# avrLCD.net
KiCad netlist of a schematic drawn in EAGLE
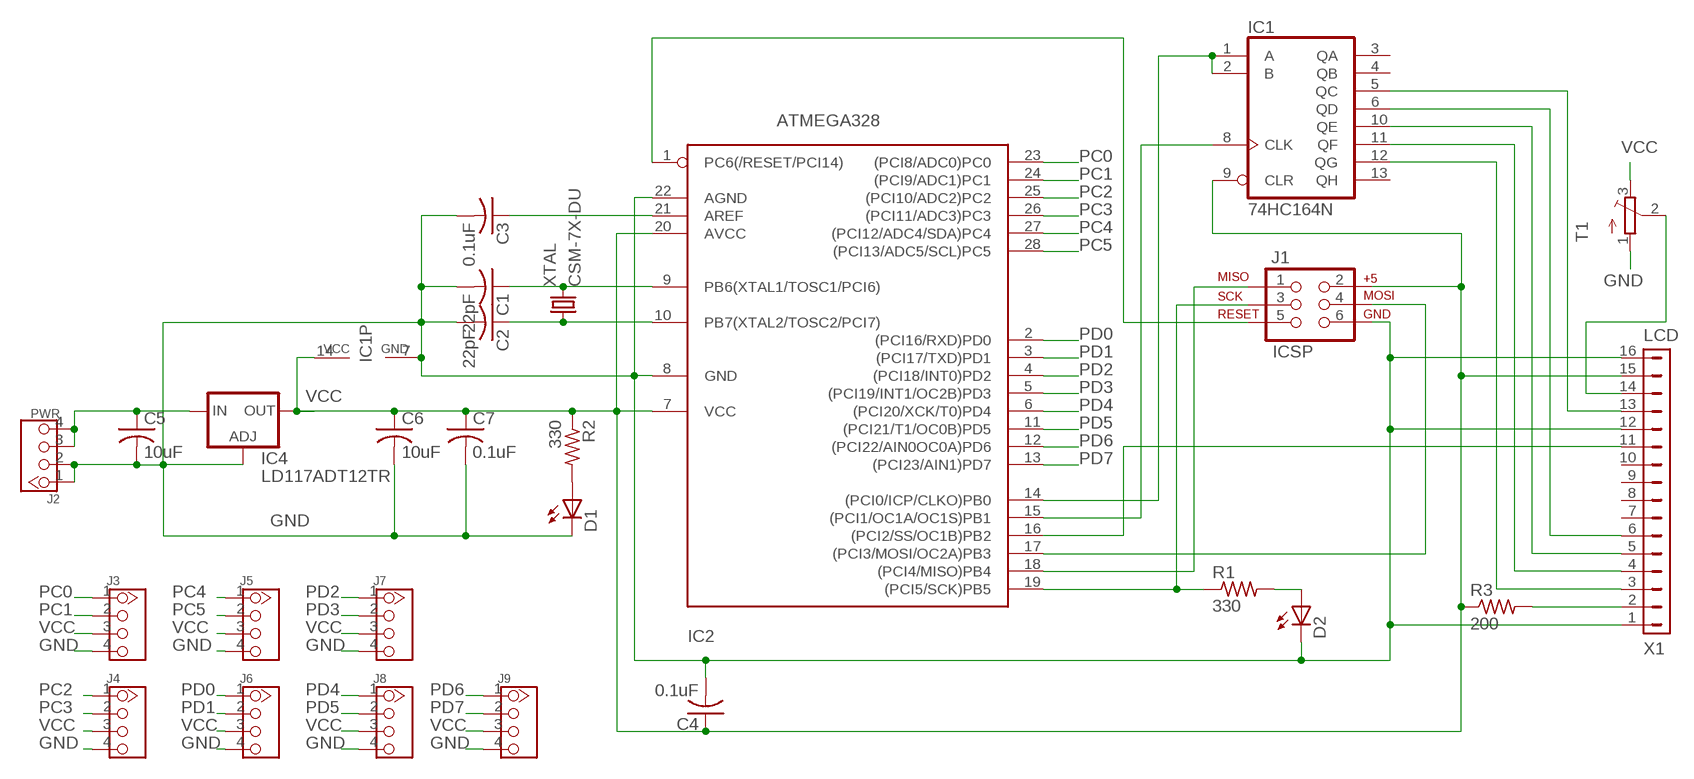
[diagram p0: schematic, sheet 1]

(export (version "E")
  (design (tool "Eeschema 10.0.6"))
  (components
    (comp (ref "C1")
      (value "22pF")
      (footprint "eagle-import:C0805")
      (libsource (lib "eagle-import") (part "C-USC0805"))
    )
    (comp (ref "C2")
      (value "22pF")
      (footprint "eagle-import:C0805")
      (libsource (lib "eagle-import") (part "C-USC0805"))
    )
    (comp (ref "C3")
      (value "0.1uF")
      (footprint "eagle-import:C0805")
      (libsource (lib "eagle-import") (part "C-USC0805"))
    )
    (comp (ref "C4")
      (value "0.1uF")
      (footprint "eagle-import:C0805")
      (libsource (lib "eagle-import") (part "C-USC0805"))
    )
    (comp (ref "C5")
      (value "10uF")
      (footprint "eagle-import:C1206")
      (libsource (lib "eagle-import") (part "C-USC1206"))
    )
    (comp (ref "C6")
      (value "10uF")
      (footprint "eagle-import:C1206")
      (libsource (lib "eagle-import") (part "C-USC1206"))
    )
    (comp (ref "C7")
      (value "0.1uF")
      (footprint "eagle-import:C0805")
      (libsource (lib "eagle-import") (part "C-USC0805"))
    )
    (comp (ref "D1")
      (value "LEDCHIP-LED0805")
      (footprint "eagle-import:CHIP-LED0805")
      (libsource (lib "eagle-import") (part "LEDCHIP-LED0805"))
    )
    (comp (ref "D2")
      (value "LEDCHIP-LED0805")
      (footprint "eagle-import:CHIP-LED0805")
      (libsource (lib "eagle-import") (part "LEDCHIP-LED0805"))
    )
    (comp (ref "IC1")
      (value "74HC164N")
      (footprint "eagle-import:DIL14")
      (libsource (lib "eagle-import") (part "74164NHC"))
    )
    (comp (ref "IC2")
      (value "ATMEGA328")
      (footprint "eagle-import:DIL28-3")
      (libsource (lib "eagle-import") (part "ATMEGA168P-20"))
    )
    (comp (ref "IC4")
      (value "LD117ADT12TR")
      (footprint "eagle-import:DPACK")
      (libsource (lib "eagle-import") (part "LD117A?DT12TR"))
    )
    (comp (ref "J1")
      (value "ICSP")
      (footprint "eagle-import:2X3-NS")
      (libsource (lib "eagle-import") (part "AVR_SPI_PRG_6NS"))
    )
    (comp (ref "J2")
      (value "PWR")
      (footprint "eagle-import:4P-2.0")
      (libsource (lib "eagle-import") (part "TWIG-4P-2.0-2.0"))
    )
    (comp (ref "J3")
      (value "TWIG-4P-2.0-2.0")
      (footprint "eagle-import:4P-2.0")
      (libsource (lib "eagle-import") (part "TWIG-4P-2.0-2.0"))
    )
    (comp (ref "J4")
      (value "TWIG-4P-2.0-2.0")
      (footprint "eagle-import:4P-2.0")
      (libsource (lib "eagle-import") (part "TWIG-4P-2.0-2.0"))
    )
    (comp (ref "J5")
      (value "TWIG-4P-2.0-2.0")
      (footprint "eagle-import:4P-2.0")
      (libsource (lib "eagle-import") (part "TWIG-4P-2.0-2.0"))
    )
    (comp (ref "J6")
      (value "TWIG-4P-2.0-2.0")
      (footprint "eagle-import:4P-2.0")
      (libsource (lib "eagle-import") (part "TWIG-4P-2.0-2.0"))
    )
    (comp (ref "J7")
      (value "TWIG-4P-2.0-2.0")
      (footprint "eagle-import:4P-2.0")
      (libsource (lib "eagle-import") (part "TWIG-4P-2.0-2.0"))
    )
    (comp (ref "J8")
      (value "TWIG-4P-2.0-2.0")
      (footprint "eagle-import:4P-2.0")
      (libsource (lib "eagle-import") (part "TWIG-4P-2.0-2.0"))
    )
    (comp (ref "J9")
      (value "TWIG-4P-2.0-2.0")
      (footprint "eagle-import:4P-2.0")
      (libsource (lib "eagle-import") (part "TWIG-4P-2.0-2.0"))
    )
    (comp (ref "R1")
      (value "330")
      (footprint "eagle-import:R0805")
      (libsource (lib "eagle-import") (part "R-US_R0805"))
    )
    (comp (ref "R2")
      (value "330")
      (footprint "eagle-import:R0805")
      (libsource (lib "eagle-import") (part "R-US_R0805"))
    )
    (comp (ref "R3")
      (value "200")
      (footprint "eagle-import:R1206")
      (libsource (lib "eagle-import") (part "R-US_R1206"))
    )
    (comp (ref "T1")
      (value "TRIMPOTTC33X")
      (footprint "eagle-import:TC33X")
      (libsource (lib "eagle-import") (part "TRIMPOTTC33X"))
    )
    (comp (ref "X1")
      (value "LCD")
      (footprint "eagle-import:FH21-16S-1DS")
      (libsource (lib "eagle-import") (part "FH21-16S-1DS"))
    )
    (comp (ref "XTAL")
      (value "CSM-7X-DU")
      (footprint "eagle-import:CSM-7X-DU")
      (libsource (lib "eagle-import") (part "CSM-7X-DU"))
    )
  )
  (nets
    (net (code "1") (name "/GND") (class "Default")
      (node (ref "C1") (pin "2") (pinfunction "2_2") (pintype "passive"))
      (node (ref "C2") (pin "2") (pinfunction "2_2") (pintype "passive"))
      (node (ref "C3") (pin "2") (pinfunction "2_2") (pintype "passive"))
      (node (ref "C4") (pin "2") (pinfunction "2_2") (pintype "passive"))
      (node (ref "C5") (pin "2") (pinfunction "2_2") (pintype "passive"))
      (node (ref "C6") (pin "2") (pinfunction "2_2") (pintype "passive"))
      (node (ref "C7") (pin "2") (pinfunction "2_2") (pintype "passive"))
      (node (ref "D1") (pin "C") (pinfunction "C_C") (pintype "passive"))
      (node (ref "D2") (pin "C") (pinfunction "C_C") (pintype "passive"))
      (node (ref "IC1") (pin "7") (pinfunction "GND_7") (pintype "power_in"))
      (node (ref "IC2") (pin "22") (pinfunction "AGND_22") (pintype "bidirectional"))
      (node (ref "IC2") (pin "8") (pinfunction "GND_8") (pintype "bidirectional"))
      (node (ref "IC4") (pin "1") (pinfunction "ADJ_1") (pintype "input"))
      (node (ref "J1") (pin "6") (pinfunction "6_6") (pintype "passive"))
      (node (ref "J2") (pin "1") (pinfunction "1_1") (pintype "bidirectional"))
      (node (ref "J2") (pin "2") (pinfunction "2_2") (pintype "bidirectional"))
      (node (ref "J3") (pin "4") (pinfunction "4_4") (pintype "bidirectional"))
      (node (ref "J4") (pin "4") (pinfunction "4_4") (pintype "bidirectional"))
      (node (ref "J5") (pin "4") (pinfunction "4_4") (pintype "bidirectional"))
      (node (ref "J6") (pin "4") (pinfunction "4_4") (pintype "bidirectional"))
      (node (ref "J7") (pin "4") (pinfunction "4_4") (pintype "bidirectional"))
      (node (ref "J8") (pin "4") (pinfunction "4_4") (pintype "bidirectional"))
      (node (ref "J9") (pin "4") (pinfunction "4_4") (pintype "bidirectional"))
      (node (ref "T1") (pin "1") (pinfunction "A_1") (pintype "passive"))
      (node (ref "X1") (pin "1") (pinfunction "1_1") (pintype "passive"))
      (node (ref "X1") (pin "12") (pinfunction "12_12") (pintype "passive"))
      (node (ref "X1") (pin "16") (pinfunction "16_16") (pintype "passive"))
    )
    (net (code "2") (name "/PC0") (class "Default")
      (node (ref "IC2") (pin "23") (pinfunction "(PCI8/ADC0)PC0_23") (pintype "bidirectional"))
      (node (ref "J3") (pin "1") (pinfunction "1_1") (pintype "bidirectional"))
    )
    (net (code "3") (name "/PC1") (class "Default")
      (node (ref "IC2") (pin "24") (pinfunction "(PCI9/ADC1)PC1_24") (pintype "bidirectional"))
      (node (ref "J3") (pin "2") (pinfunction "2_2") (pintype "bidirectional"))
    )
    (net (code "4") (name "/PC2") (class "Default")
      (node (ref "IC2") (pin "25") (pinfunction "(PCI10/ADC2)PC2_25") (pintype "bidirectional"))
      (node (ref "J4") (pin "1") (pinfunction "1_1") (pintype "bidirectional"))
    )
    (net (code "5") (name "/PC3") (class "Default")
      (node (ref "IC2") (pin "26") (pinfunction "(PCI11/ADC3)PC3_26") (pintype "bidirectional"))
      (node (ref "J4") (pin "2") (pinfunction "2_2") (pintype "bidirectional"))
    )
    (net (code "6") (name "/PC4") (class "Default")
      (node (ref "IC2") (pin "27") (pinfunction "(PCI12/ADC4/SDA)PC4_27") (pintype "bidirectional"))
      (node (ref "J5") (pin "1") (pinfunction "1_1") (pintype "bidirectional"))
    )
    (net (code "7") (name "/PC5") (class "Default")
      (node (ref "IC2") (pin "28") (pinfunction "(PCI13/ADC5/SCL)PC5_28") (pintype "bidirectional"))
      (node (ref "J5") (pin "2") (pinfunction "2_2") (pintype "bidirectional"))
    )
    (net (code "8") (name "/PD0") (class "Default")
      (node (ref "IC2") (pin "2") (pinfunction "(PCI16/RXD)PD0_2") (pintype "bidirectional"))
      (node (ref "J6") (pin "1") (pinfunction "1_1") (pintype "bidirectional"))
    )
    (net (code "9") (name "/PD1") (class "Default")
      (node (ref "IC2") (pin "3") (pinfunction "(PCI17/TXD)PD1_3") (pintype "bidirectional"))
      (node (ref "J6") (pin "2") (pinfunction "2_2") (pintype "bidirectional"))
    )
    (net (code "10") (name "/PD2") (class "Default")
      (node (ref "IC2") (pin "4") (pinfunction "(PCI18/INT0)PD2_4") (pintype "bidirectional"))
      (node (ref "J7") (pin "1") (pinfunction "1_1") (pintype "bidirectional"))
    )
    (net (code "11") (name "/PD3") (class "Default")
      (node (ref "IC2") (pin "5") (pinfunction "(PCI19/INT1/OC2B)PD3_5") (pintype "bidirectional"))
      (node (ref "J7") (pin "2") (pinfunction "2_2") (pintype "bidirectional"))
    )
    (net (code "12") (name "/PD4") (class "Default")
      (node (ref "IC2") (pin "6") (pinfunction "(PCI20/XCK/T0)PD4_6") (pintype "bidirectional"))
      (node (ref "J8") (pin "1") (pinfunction "1_1") (pintype "bidirectional"))
    )
    (net (code "13") (name "/PD5") (class "Default")
      (node (ref "IC2") (pin "11") (pinfunction "(PCI21/T1/OC0B)PD5_11") (pintype "bidirectional"))
      (node (ref "J8") (pin "2") (pinfunction "2_2") (pintype "bidirectional"))
    )
    (net (code "14") (name "/PD6") (class "Default")
      (node (ref "IC2") (pin "12") (pinfunction "(PCI22/AIN0OC0A)PD6_12") (pintype "bidirectional"))
      (node (ref "J9") (pin "1") (pinfunction "1_1") (pintype "bidirectional"))
    )
    (net (code "15") (name "/PD7") (class "Default")
      (node (ref "IC2") (pin "13") (pinfunction "(PCI23/AIN1)PD7_13") (pintype "bidirectional"))
      (node (ref "J9") (pin "2") (pinfunction "2_2") (pintype "bidirectional"))
    )
    (net (code "16") (name "/VCC") (class "Default")
      (node (ref "C4") (pin "1") (pinfunction "1_1") (pintype "passive"))
      (node (ref "C6") (pin "1") (pinfunction "1_1") (pintype "passive"))
      (node (ref "C7") (pin "1") (pinfunction "1_1") (pintype "passive"))
      (node (ref "IC1") (pin "14") (pinfunction "VCC_14") (pintype "power_in"))
      (node (ref "IC1") (pin "9") (pinfunction "CLR_9") (pintype "input"))
      (node (ref "IC2") (pin "20") (pinfunction "AVCC_20") (pintype "bidirectional"))
      (node (ref "IC2") (pin "7") (pinfunction "VCC_7") (pintype "bidirectional"))
      (node (ref "IC4") (pin "4") (pinfunction "OUT_4") (pintype "passive"))
      (node (ref "J1") (pin "2") (pinfunction "2_2") (pintype "passive"))
      (node (ref "J3") (pin "3") (pinfunction "3_3") (pintype "bidirectional"))
      (node (ref "J4") (pin "3") (pinfunction "3_3") (pintype "bidirectional"))
      (node (ref "J5") (pin "3") (pinfunction "3_3") (pintype "bidirectional"))
      (node (ref "J6") (pin "3") (pinfunction "3_3") (pintype "bidirectional"))
      (node (ref "J7") (pin "3") (pinfunction "3_3") (pintype "bidirectional"))
      (node (ref "J8") (pin "3") (pinfunction "3_3") (pintype "bidirectional"))
      (node (ref "J9") (pin "3") (pinfunction "3_3") (pintype "bidirectional"))
      (node (ref "R2") (pin "1") (pinfunction "1_1") (pintype "passive"))
      (node (ref "R3") (pin "1") (pinfunction "1_1") (pintype "passive"))
      (node (ref "T1") (pin "3") (pinfunction "E_3") (pintype "passive"))
      (node (ref "X1") (pin "15") (pinfunction "15_15") (pintype "passive"))
    )
    (net (code "17") (name "Net-(D1-PadA)") (class "Default")
      (node (ref "D1") (pin "A") (pinfunction "A_A") (pintype "passive"))
      (node (ref "R2") (pin "2") (pinfunction "2_2") (pintype "passive"))
    )
    (net (code "18") (name "Net-(D2-PadA)") (class "Default")
      (node (ref "D2") (pin "A") (pinfunction "A_A") (pintype "passive"))
      (node (ref "R1") (pin "2") (pinfunction "2_2") (pintype "passive"))
    )
    (net (code "19") (name "Net-(IC1A-A)") (class "Default")
      (node (ref "IC1") (pin "1") (pinfunction "A_1") (pintype "input"))
      (node (ref "IC1") (pin "2") (pinfunction "B_2") (pintype "input"))
      (node (ref "IC2") (pin "14") (pinfunction "(PCI0/ICP/CLKO)PB0_14") (pintype "bidirectional"))
    )
    (net (code "20") (name "Net-(IC1A-CLK)") (class "Default")
      (node (ref "IC1") (pin "8") (pinfunction "CLK_8") (pintype "input"))
      (node (ref "IC2") (pin "15") (pinfunction "(PCI1/OC1A/OC1S)PB1_15") (pintype "bidirectional"))
    )
    (net (code "21") (name "Net-(IC1A-QC)") (class "Default")
      (node (ref "IC1") (pin "5") (pinfunction "QC_5") (pintype "output"))
      (node (ref "X1") (pin "13") (pinfunction "13_13") (pintype "passive"))
    )
    (net (code "22") (name "Net-(IC1A-QD)") (class "Default")
      (node (ref "IC1") (pin "6") (pinfunction "QD_6") (pintype "output"))
      (node (ref "X1") (pin "6") (pinfunction "6_6") (pintype "passive"))
    )
    (net (code "23") (name "Net-(IC1A-QE)") (class "Default")
      (node (ref "IC1") (pin "10") (pinfunction "QE_10") (pintype "output"))
      (node (ref "X1") (pin "5") (pinfunction "5_5") (pintype "passive"))
    )
    (net (code "24") (name "Net-(IC1A-QF)") (class "Default")
      (node (ref "IC1") (pin "11") (pinfunction "QF_11") (pintype "output"))
      (node (ref "X1") (pin "4") (pinfunction "4_4") (pintype "passive"))
    )
    (net (code "25") (name "Net-(IC1A-QG)") (class "Default")
      (node (ref "IC1") (pin "12") (pinfunction "QG_12") (pintype "output"))
      (node (ref "X1") (pin "3") (pinfunction "3_3") (pintype "passive"))
    )
    (net (code "26") (name "Net-(IC2-(PCI2{slash}SS{slash}OC1B)PB2)") (class "Default")
      (node (ref "IC2") (pin "16") (pinfunction "(PCI2/SS/OC1B)PB2_16") (pintype "bidirectional"))
      (node (ref "X1") (pin "11") (pinfunction "11_11") (pintype "passive"))
    )
    (net (code "27") (name "Net-(IC2-(PCI3{slash}MOSI{slash}OC2A)PB3)") (class "Default")
      (node (ref "IC2") (pin "17") (pinfunction "(PCI3/MOSI/OC2A)PB3_17") (pintype "bidirectional"))
      (node (ref "J1") (pin "4") (pinfunction "4_4") (pintype "passive"))
    )
    (net (code "28") (name "Net-(IC2-(PCI4{slash}MISO)PB4)") (class "Default")
      (node (ref "IC2") (pin "18") (pinfunction "(PCI4/MISO)PB4_18") (pintype "bidirectional"))
      (node (ref "J1") (pin "1") (pinfunction "1_1") (pintype "passive"))
    )
    (net (code "29") (name "Net-(IC2-(PCI5{slash}SCK)PB5)") (class "Default")
      (node (ref "IC2") (pin "19") (pinfunction "(PCI5/SCK)PB5_19") (pintype "bidirectional"))
      (node (ref "J1") (pin "3") (pinfunction "3_3") (pintype "passive"))
      (node (ref "R1") (pin "1") (pinfunction "1_1") (pintype "passive"))
    )
    (net (code "30") (name "Net-(IC2-AREF)") (class "Default")
      (node (ref "C3") (pin "1") (pinfunction "1_1") (pintype "passive"))
      (node (ref "IC2") (pin "21") (pinfunction "AREF_21") (pintype "bidirectional"))
    )
    (net (code "31") (name "Net-(IC2-PB6(XTAL1{slash}TOSC1{slash}PCI6))") (class "Default")
      (node (ref "C1") (pin "1") (pinfunction "1_1") (pintype "passive"))
      (node (ref "IC2") (pin "9") (pinfunction "PB6(XTAL1/TOSC1/PCI6)_9") (pintype "bidirectional"))
      (node (ref "XTAL") (pin "2") (pinfunction "2_2") (pintype "passive"))
    )
    (net (code "32") (name "Net-(IC2-PB7(XTAL2{slash}TOSC2{slash}PCI7))") (class "Default")
      (node (ref "C2") (pin "1") (pinfunction "1_1") (pintype "passive"))
      (node (ref "IC2") (pin "10") (pinfunction "PB7(XTAL2/TOSC2/PCI7)_10") (pintype "bidirectional"))
      (node (ref "XTAL") (pin "1") (pinfunction "1_1") (pintype "passive"))
    )
    (net (code "33") (name "Net-(IC2-PC6({slash}RESET{slash}PCI14))") (class "Default")
      (node (ref "IC2") (pin "1") (pinfunction "PC6(/RESET/PCI14)_1") (pintype "bidirectional"))
      (node (ref "J1") (pin "5") (pinfunction "5_5") (pintype "passive"))
    )
    (net (code "34") (name "Net-(IC4-IN)") (class "Default")
      (node (ref "C5") (pin "1") (pinfunction "1_1") (pintype "passive"))
      (node (ref "IC4") (pin "3") (pinfunction "IN_3") (pintype "input"))
      (node (ref "J2") (pin "3") (pinfunction "3_3") (pintype "bidirectional"))
      (node (ref "J2") (pin "4") (pinfunction "4_4") (pintype "bidirectional"))
    )
    (net (code "35") (name "Net-(R3-Pad2)") (class "Default")
      (node (ref "R3") (pin "2") (pinfunction "2_2") (pintype "passive"))
      (node (ref "X1") (pin "2") (pinfunction "2_2") (pintype "passive"))
    )
    (net (code "36") (name "Net-(T1-S)") (class "Default")
      (node (ref "T1") (pin "2") (pinfunction "S_2") (pintype "passive"))
      (node (ref "X1") (pin "14") (pinfunction "14_14") (pintype "passive"))
    )
    (net (code "37") (name "unconnected-(IC1A-QA-Pad3)") (class "Default")
      (node (ref "IC1") (pin "3") (pinfunction "QA_3") (pintype "output"))
    )
    (net (code "38") (name "unconnected-(IC1A-QB-Pad4)") (class "Default")
      (node (ref "IC1") (pin "4") (pinfunction "QB_4") (pintype "output"))
    )
    (net (code "39") (name "unconnected-(IC1A-QH-Pad13)") (class "Default")
      (node (ref "IC1") (pin "13") (pinfunction "QH_13") (pintype "output"))
    )
    (net (code "40") (name "unconnected-(X1-Pad7)") (class "Default")
      (node (ref "X1") (pin "7") (pinfunction "7_7") (pintype "passive"))
    )
    (net (code "41") (name "unconnected-(X1-Pad8)") (class "Default")
      (node (ref "X1") (pin "8") (pinfunction "8_8") (pintype "passive"))
    )
    (net (code "42") (name "unconnected-(X1-Pad9)") (class "Default")
      (node (ref "X1") (pin "9") (pinfunction "9_9") (pintype "passive"))
    )
    (net (code "43") (name "unconnected-(X1-Pad10)") (class "Default")
      (node (ref "X1") (pin "10") (pinfunction "10_10") (pintype "passive"))
    )
  )
)
